# Connector.net
KiCad netlist of a schematic drawn in Altium Designer
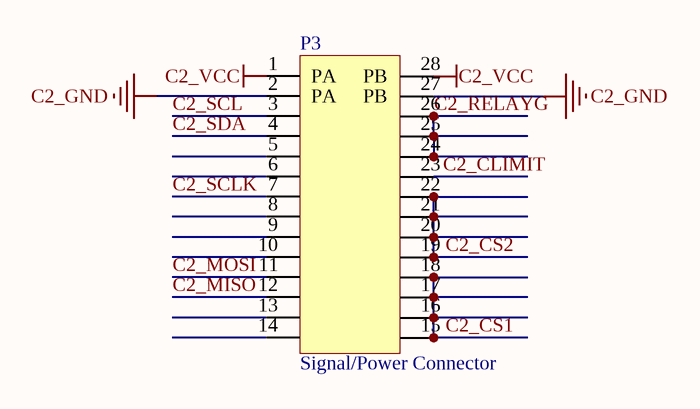
[diagram p0: Connector.SchDoc]

(export (version "E")
  (design (tool "Eeschema 10.0.6"))
  (components
    (comp (ref "P3")
      (value "Signal/Power Connector")
      (footprint "Signal/Power Connector")
      (libsource (lib "Power Supply Library") (part "Signal/Power Connector"))
    )
  )
  (nets
    (net (code "1") (name "/C2_CLIMIT") (class "Default")
      (node (ref "P3") (pin "23") (pinfunction "23_23") (pintype "passive"))
    )
    (net (code "2") (name "/C2_CS1") (class "Default")
      (node (ref "P3") (pin "15") (pinfunction "15_15") (pintype "passive"))
      (node (ref "P3") (pin "16") (pinfunction "16_16") (pintype "passive"))
      (node (ref "P3") (pin "17") (pinfunction "17_17") (pintype "passive"))
      (node (ref "P3") (pin "18") (pinfunction "18_18") (pintype "passive"))
    )
    (net (code "3") (name "/C2_CS2") (class "Default")
      (node (ref "P3") (pin "19") (pinfunction "19_19") (pintype "passive"))
      (node (ref "P3") (pin "20") (pinfunction "20_20") (pintype "passive"))
      (node (ref "P3") (pin "21") (pinfunction "21_21") (pintype "passive"))
      (node (ref "P3") (pin "22") (pinfunction "22_22") (pintype "passive"))
    )
    (net (code "4") (name "/C2_MISO") (class "Default")
      (node (ref "P3") (pin "12") (pinfunction "12_12") (pintype "passive"))
    )
    (net (code "5") (name "/C2_MOSI") (class "Default")
      (node (ref "P3") (pin "11") (pinfunction "11_11") (pintype "passive"))
    )
    (net (code "6") (name "/C2_RELAYG") (class "Default")
      (node (ref "P3") (pin "24") (pinfunction "24_24") (pintype "passive"))
      (node (ref "P3") (pin "25") (pinfunction "25_25") (pintype "passive"))
      (node (ref "P3") (pin "26") (pinfunction "26_26") (pintype "passive"))
    )
    (net (code "7") (name "/C2_SCL") (class "Default")
      (node (ref "P3") (pin "3") (pinfunction "3_3") (pintype "passive"))
    )
    (net (code "8") (name "/C2_SCLK") (class "Default")
      (node (ref "P3") (pin "7") (pinfunction "7_7") (pintype "passive"))
    )
    (net (code "9") (name "/C2_SDA") (class "Default")
      (node (ref "P3") (pin "4") (pinfunction "4_4") (pintype "passive"))
    )
    (net (code "10") (name "C2_GND") (class "Default")
      (node (ref "P3") (pin "2") (pinfunction "PA_2") (pintype "passive"))
      (node (ref "P3") (pin "27") (pinfunction "PB_27") (pintype "passive"))
    )
    (net (code "11") (name "C2_VCC") (class "Default")
      (node (ref "P3") (pin "1") (pinfunction "PA_1") (pintype "passive"))
      (node (ref "P3") (pin "28") (pinfunction "PB_28") (pintype "passive"))
    )
    (net (code "12") (name "unconnected-(P3-Pad5)") (class "Default")
      (node (ref "P3") (pin "5") (pinfunction "5_5") (pintype "passive"))
    )
    (net (code "13") (name "unconnected-(P3-Pad6)") (class "Default")
      (node (ref "P3") (pin "6") (pinfunction "6_6") (pintype "passive"))
    )
    (net (code "14") (name "unconnected-(P3-Pad8)") (class "Default")
      (node (ref "P3") (pin "8") (pinfunction "8_8") (pintype "passive"))
    )
    (net (code "15") (name "unconnected-(P3-Pad9)") (class "Default")
      (node (ref "P3") (pin "9") (pinfunction "9_9") (pintype "passive"))
    )
    (net (code "16") (name "unconnected-(P3-Pad10)") (class "Default")
      (node (ref "P3") (pin "10") (pinfunction "10_10") (pintype "passive"))
    )
    (net (code "17") (name "unconnected-(P3-Pad13)") (class "Default")
      (node (ref "P3") (pin "13") (pinfunction "13_13") (pintype "passive"))
    )
    (net (code "18") (name "unconnected-(P3-Pad14)") (class "Default")
      (node (ref "P3") (pin "14") (pinfunction "14_14") (pintype "passive"))
    )
  )
)
